# 5V_BUCK.net
KiCad netlist of a schematic drawn in Altium Designer
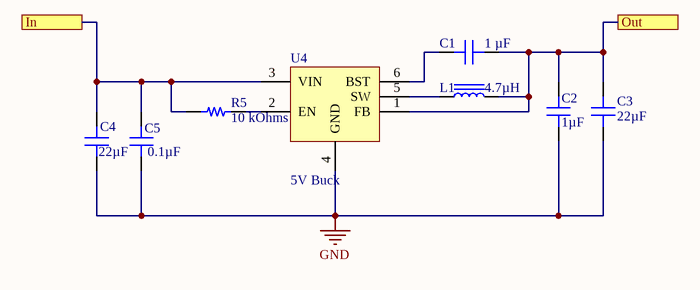
[diagram p0: 5V_BUCK.SchDoc]

(export (version "E")
  (design (tool "Eeschema 10.0.6"))
  (components
    (comp (ref "C1")
      (value "1 µF")
      (footprint "CAP 0402_1005")
      (description "CAP CER 0.1UF 16V X7R 0402")
      (fields (field (name "PART NUMBER") "C0402C104K4RACAUTO") (field (name "MANUFACTURER") "KEMET"))
      (libsource (lib "Celestial Altium Library - altium_library") (part "Capacitor"))
    )
    (comp (ref "C2")
      (value "1µF")
      (footprint "CAP 0603_1608")
      (description "CAP CER 1UF 25V X7R 0603")
      (fields
        (field (name "PART NUMBER") "GCJ188R71E105KA01D")
        (field (name "MANUFACTURER") "Murata Electronics")
      )
      (libsource (lib "Celestial Altium Library - altium_library") (part "Capacitor"))
    )
    (comp (ref "C3")
      (value "22µF")
      (footprint "CAP 0805_2012")
      (description "CAP CER 22UF 16V X5R 0805")
      (fields
        (field (name "PART NUMBER") "CL21A226MOQNNNE")
        (field (name "MANUFACTURER") "Samsung Electro-Mechanics")
      )
      (libsource (lib "Celestial Altium Library - altium_library") (part "Capacitor"))
    )
    (comp (ref "C4")
      (value "22µF")
      (footprint "CAP 0805_2012")
      (description "CAP CER 10UF 25V X7S 0805")
      (fields
        (field (name "PART NUMBER") "C2012X7S1E106K125AC")
        (field (name "MANUFACTURER") "TDK Corporation")
      )
      (libsource (lib "Celestial Altium Library - altium_library") (part "Capacitor"))
    )
    (comp (ref "C5")
      (value "0.1µF")
      (footprint "CAP 0603_1608")
      (description "CAP CER 0.1UF 100V 0603 EPOXY")
      (fields
        (field (name "PART NUMBER") "GCG188R92A104KA03D")
        (field (name "MANUFACTURER") "Murata Electronics")
      )
      (libsource (lib "Celestial Altium Library - altium_library") (part "Capacitor"))
    )
    (comp (ref "L1")
      (value "4.7µH")
      (footprint "IND 1008_2520")
      (description "FIXED IND 4.7UH 1A 110 MOHM SMD")
      (fields (field (name "PART NUMBER") "MLP2520S4R7ST0S1") (field (name "MANUFACTURER") "TDK Corporation"))
      (libsource (lib "Celestial Altium Library - altium_library") (part "Inductor"))
    )
    (comp (ref "R5")
      (value "10 kOhms")
      (footprint "RES 0402_1005")
      (description "RES 14.3K OHM 1% 1/10W 0402")
      (fields
        (field (name "PART NUMBER") "RK73H1ETTP1432F")
        (field (name "MANUFACTURER") "KOA Speer Electronics, Inc.")
      )
      (libsource (lib "Celestial Altium Library - altium_library") (part "Resistor"))
    )
    (comp (ref "U4")
      (value "5V Buck")
      (footprint "TSOT-26-6 - 3.2mm")
      (description "5V fixed step down Buck")
      (libsource (lib "IC") (part "AP63205WU-7"))
    )
  )
  (nets
    (net (code "1") (name "/In") (class "Default")
      (node (ref "C4") (pin "2") (pinfunction "2_2") (pintype "passive"))
      (node (ref "C5") (pin "1") (pinfunction "1_1") (pintype "passive"))
      (node (ref "R5") (pin "1") (pinfunction "1_1") (pintype "passive"))
      (node (ref "U4") (pin "3") (pinfunction "VIN_3") (pintype "passive"))
    )
    (net (code "2") (name "/Out") (class "Default")
      (node (ref "C1") (pin "2") (pinfunction "2_2") (pintype "passive"))
      (node (ref "C2") (pin "2") (pinfunction "2_2") (pintype "passive"))
      (node (ref "C3") (pin "2") (pinfunction "2_2") (pintype "passive"))
      (node (ref "L1") (pin "2") (pinfunction "2_2") (pintype "passive"))
      (node (ref "U4") (pin "1") (pinfunction "FB_1") (pintype "passive"))
    )
    (net (code "3") (name "GND") (class "Default")
      (node (ref "C2") (pin "1") (pinfunction "1_1") (pintype "passive"))
      (node (ref "C3") (pin "1") (pinfunction "1_1") (pintype "passive"))
      (node (ref "C4") (pin "1") (pinfunction "1_1") (pintype "passive"))
      (node (ref "C5") (pin "2") (pinfunction "2_2") (pintype "passive"))
      (node (ref "U4") (pin "4") (pinfunction "GND_4") (pintype "passive"))
    )
    (net (code "4") (name "Net-(U4-BST)") (class "Default")
      (node (ref "C1") (pin "1") (pinfunction "1_1") (pintype "passive"))
      (node (ref "U4") (pin "6") (pinfunction "BST_6") (pintype "passive"))
    )
    (net (code "5") (name "Net-(U4-EN)") (class "Default")
      (node (ref "R5") (pin "2") (pinfunction "2_2") (pintype "passive"))
      (node (ref "U4") (pin "2") (pinfunction "EN_2") (pintype "passive"))
    )
    (net (code "6") (name "Net-(U4-SW)") (class "Default")
      (node (ref "L1") (pin "1") (pinfunction "1_1") (pintype "passive"))
      (node (ref "U4") (pin "5") (pinfunction "SW_5") (pintype "passive"))
    )
  )
)
